# SH9_-_RS-485.net
KiCad netlist of a schematic drawn in Altium Designer
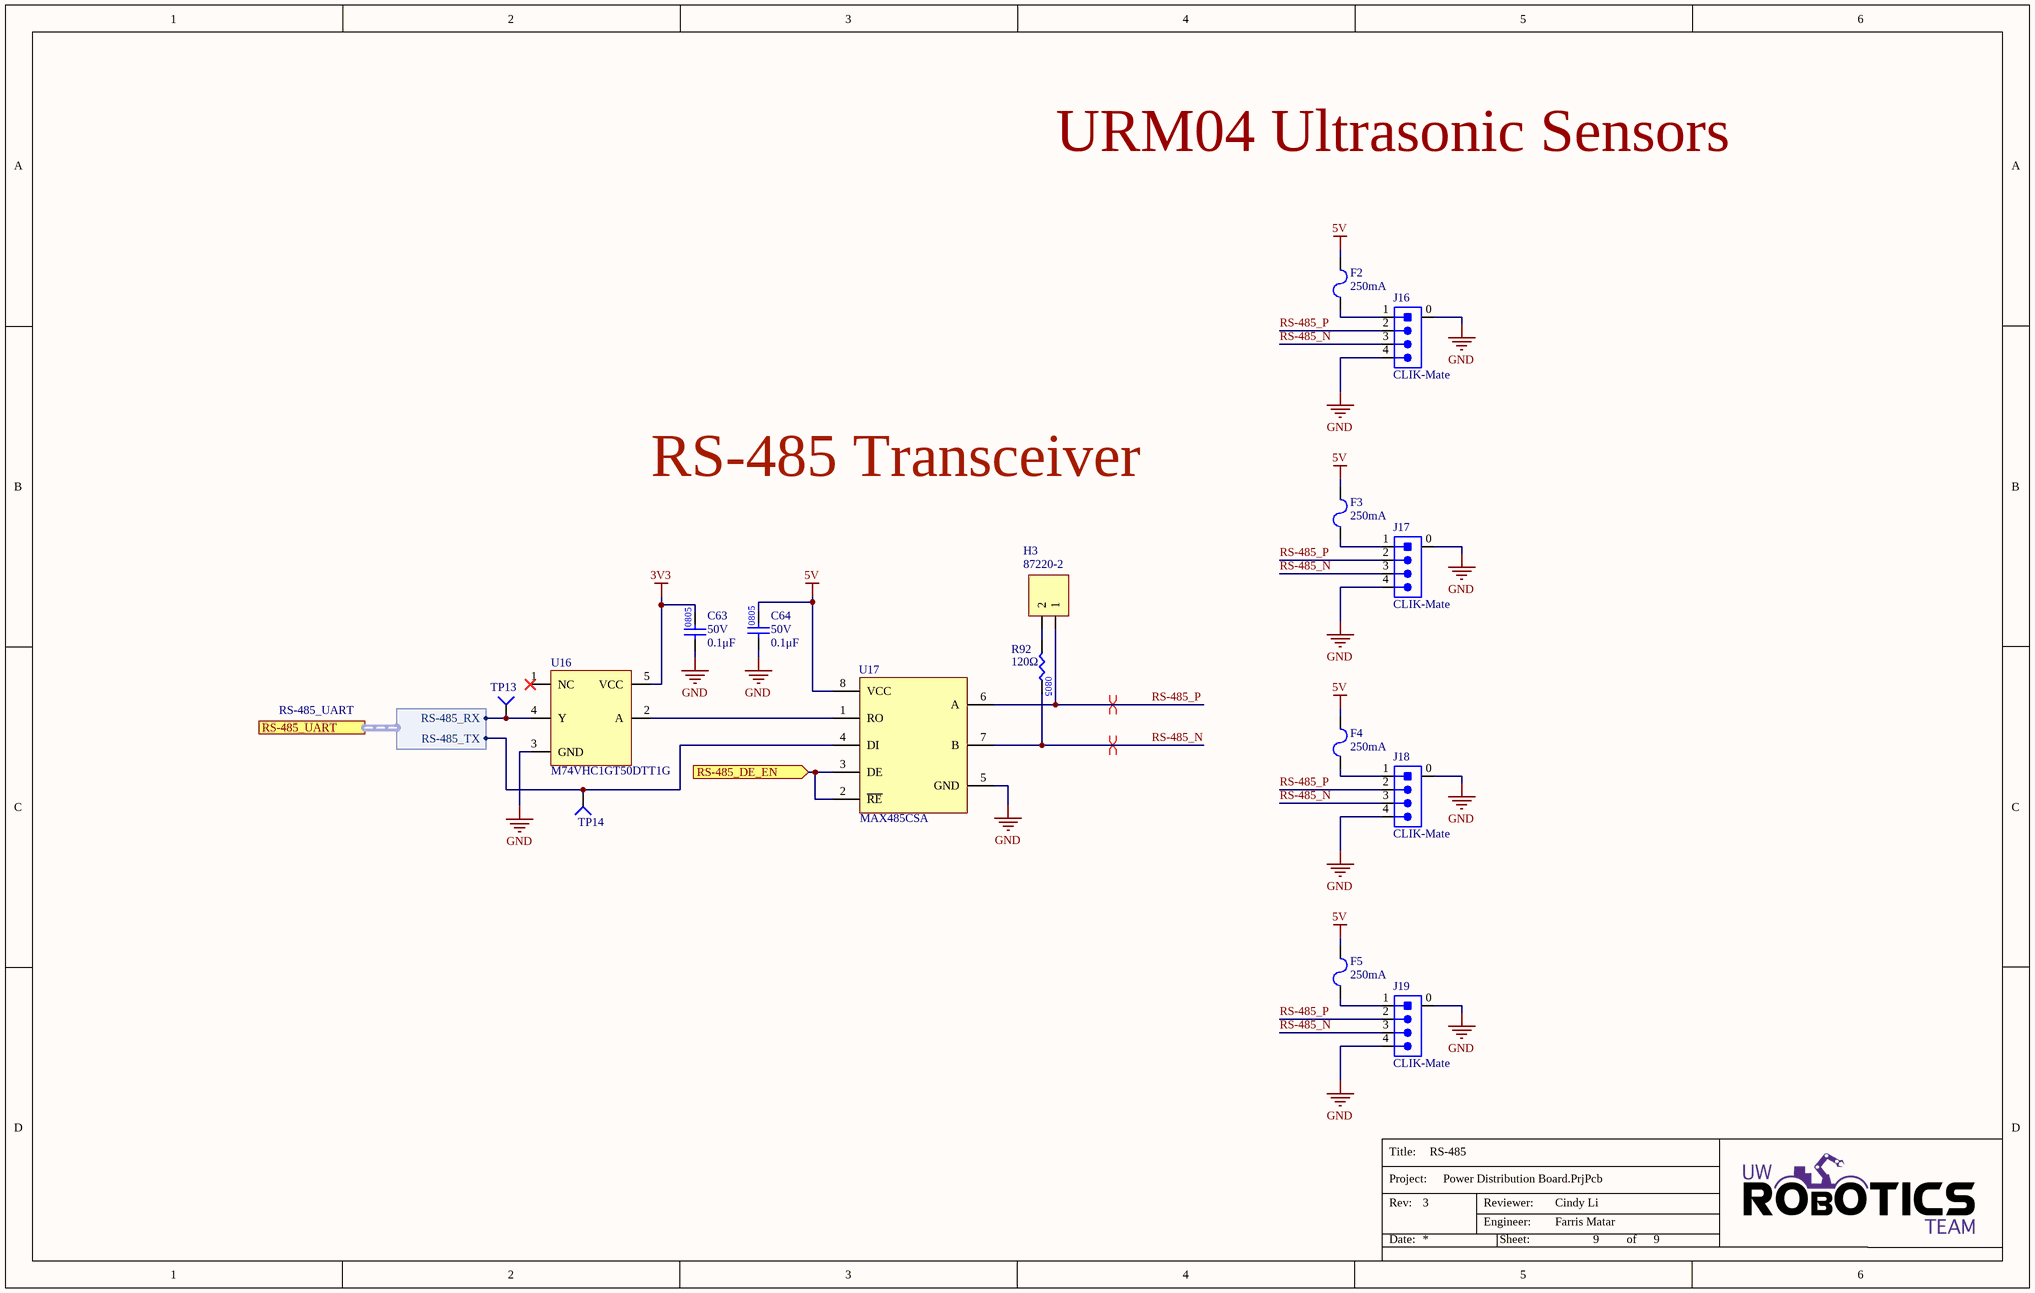
[diagram p0: SH9 - RS-485.SchDoc]

(export (version "E")
  (design (tool "Eeschema 10.0.6"))
  (components
    (comp (ref "C63")
      (value "0.1μF")
      (footprint "CAP2012")
      (description "CAP CER 0.1UF 50V X7R 0805")
      (fields
        (field (name "VOLTAGE RATING") "50V")
        (field (name "LCSC PART #") "C49678")
        (field (name "Comment") "CAP_0.1uF_50V_0805")
      )
      (libsource (lib "UWRT_Schematic_Library_2020") (part "CAP_0.1uF_50V_0805"))
    )
    (comp (ref "C64")
      (value "0.1μF")
      (footprint "CAP2012")
      (description "CAP CER 0.1UF 50V X7R 0805")
      (fields
        (field (name "VOLTAGE RATING") "50V")
        (field (name "LCSC PART #") "C49678")
        (field (name "Comment") "CAP_0.1uF_50V_0805")
      )
      (libsource (lib "UWRT_Schematic_Library_2020") (part "CAP_0.1uF_50V_0805"))
    )
    (comp (ref "F2")
      (value "FUSE_250mA_1206")
      (footprint "FUSE_1206")
      (description "FUSE BOARD MNT 250MA 125VAC/VDC")
      (fields (field (name "CURRENT RATING") "250mA"))
      (libsource (lib "UWRT_Schematic_Library_2020") (part "FUSE_250mA_1206"))
    )
    (comp (ref "F3")
      (value "FUSE_250mA_1206")
      (footprint "FUSE_1206")
      (description "FUSE BOARD MNT 250MA 125VAC/VDC")
      (fields (field (name "CURRENT RATING") "250mA"))
      (libsource (lib "UWRT_Schematic_Library_2020") (part "FUSE_250mA_1206"))
    )
    (comp (ref "F4")
      (value "FUSE_250mA_1206")
      (footprint "FUSE_1206")
      (description "FUSE BOARD MNT 250MA 125VAC/VDC")
      (fields (field (name "CURRENT RATING") "250mA"))
      (libsource (lib "UWRT_Schematic_Library_2020") (part "FUSE_250mA_1206"))
    )
    (comp (ref "F5")
      (value "FUSE_250mA_1206")
      (footprint "FUSE_1206")
      (description "FUSE BOARD MNT 250MA 125VAC/VDC")
      (fields (field (name "CURRENT RATING") "250mA"))
      (libsource (lib "UWRT_Schematic_Library_2020") (part "FUSE_250mA_1206"))
    )
    (comp (ref "H3")
      (value "JUMPER_2")
      (footprint "HDR1X2")
      (description "HEADER 2X1")
      (fields (field (name "MANUFACTURER PART NUMBER 1") "87220-2"))
      (libsource (lib "UWRT_Schematic_Library_2020") (part "JUMPER_2"))
    )
    (comp (ref "J16")
      (value "CON_4M_SM_RA")
      (footprint "MOLEX-5025850470")
      (description "CONN HEADER SMD RIGHT ANGLE 1.5 MM PITCH")
      (fields (field (name "FAMILY") "CLIK-Mate"))
      (libsource (lib "UWRT_Schematic_Library_2020") (part "CON_4M_SM_RA"))
    )
    (comp (ref "J17")
      (value "CON_4M_SM_RA")
      (footprint "MOLEX-5025850470")
      (description "CONN HEADER SMD RIGHT ANGLE 1.5 MM PITCH")
      (fields (field (name "FAMILY") "CLIK-Mate"))
      (libsource (lib "UWRT_Schematic_Library_2020") (part "CON_4M_SM_RA"))
    )
    (comp (ref "J18")
      (value "CON_4M_SM_RA")
      (footprint "MOLEX-5025850470")
      (description "CONN HEADER SMD RIGHT ANGLE 1.5 MM PITCH")
      (fields (field (name "FAMILY") "CLIK-Mate"))
      (libsource (lib "UWRT_Schematic_Library_2020") (part "CON_4M_SM_RA"))
    )
    (comp (ref "J19")
      (value "CON_4M_SM_RA")
      (footprint "MOLEX-5025850470")
      (description "CONN HEADER SMD RIGHT ANGLE 1.5 MM PITCH")
      (fields (field (name "FAMILY") "CLIK-Mate"))
      (libsource (lib "UWRT_Schematic_Library_2020") (part "CON_4M_SM_RA"))
    )
    (comp (ref "R92")
      (value "120Ω")
      (footprint "RES0805")
      (description "RES 120 OHM 1% 1/8W 0805")
      (fields (field (name "LCSC PART #") "C17437") (field (name "Comment") "RES_120Ω_0805_1%"))
      (libsource (lib "UWRT_Schematic_Library_2020") (part "RES_120Ω_0805_1%"))
    )
    (comp (ref "TP13")
      (value "TESTPOINT_1MM_CIRCLE")
      (footprint "TESTPOINT_CIRCLE_1MM")
      (description "TESTPOINT 1MM CIRCLE")
      (libsource (lib "UWRT_Schematic_Library_2020") (part "TESTPOINT_1MM_CIRCLE"))
    )
    (comp (ref "TP14")
      (value "TESTPOINT_1MM_CIRCLE")
      (footprint "TESTPOINT_CIRCLE_1MM")
      (description "TESTPOINT 1MM CIRCLE")
      (libsource (lib "UWRT_Schematic_Library_2020") (part "TESTPOINT_1MM_CIRCLE"))
    )
    (comp (ref "U16")
      (value "IC_BUFFER_TSOP5")
      (footprint "SN74LV1T34DBVR")
      (description "IC BUFFER NON-INVERT 5.5V 5TSOP")
      (fields (field (name "MANUFACTURER PART NUMBER 1") "M74VHC1GT50DTT1G"))
      (libsource (lib "UWRT_Schematic_Library_2020") (part "IC_BUFFER_TSOP5"))
    )
    (comp (ref "U17")
      (value "MAX485CSA")
      (footprint "SOIC127P600X175-8N")
      (description "IC RS485 TRANSCEIVER HALF 1/1 8SOIC")
      (fields (field (name "LCSC PART #") "C9945"))
      (libsource (lib "UWRT_Schematic_Library_2020") (part "MAX485CSA"))
    )
  )
  (nets
    (net (code "2") (name "/RS-485_DE_EN") (class "Default")
      (node (ref "U17") (pin "2") (pinfunction "~{RE}_2") (pintype "passive"))
      (node (ref "U17") (pin "3") (pinfunction "DE_3") (pintype "passive"))
    )
    (net (code "3") (name "/RS-485_N") (class "Default")
      (node (ref "J16") (pin "3") (pinfunction "3_3") (pintype "passive"))
      (node (ref "J17") (pin "3") (pinfunction "3_3") (pintype "passive"))
      (node (ref "J18") (pin "3") (pinfunction "3_3") (pintype "passive"))
      (node (ref "J19") (pin "3") (pinfunction "3_3") (pintype "passive"))
      (node (ref "R92") (pin "2") (pinfunction "2_2") (pintype "passive"))
      (node (ref "U17") (pin "7") (pinfunction "B_7") (pintype "passive"))
    )
    (net (code "4") (name "/RS-485_P") (class "Default")
      (node (ref "H3") (pin "1") (pinfunction "1_1") (pintype "passive"))
      (node (ref "J16") (pin "2") (pinfunction "2_2") (pintype "passive"))
      (node (ref "J17") (pin "2") (pinfunction "2_2") (pintype "passive"))
      (node (ref "J18") (pin "2") (pinfunction "2_2") (pintype "passive"))
      (node (ref "J19") (pin "2") (pinfunction "2_2") (pintype "passive"))
      (node (ref "U17") (pin "6") (pinfunction "A_6") (pintype "passive"))
    )
    (net (code "6") (name "3V3") (class "Default")
      (node (ref "C63") (pin "2") (pinfunction "2_2") (pintype "passive"))
      (node (ref "U16") (pin "5") (pinfunction "VCC_5") (pintype "passive"))
    )
    (net (code "7") (name "5V") (class "Default")
      (node (ref "C64") (pin "2") (pinfunction "2_2") (pintype "passive"))
      (node (ref "F2") (pin "2") (pinfunction "2_2") (pintype "passive"))
      (node (ref "F3") (pin "2") (pinfunction "2_2") (pintype "passive"))
      (node (ref "F4") (pin "2") (pinfunction "2_2") (pintype "passive"))
      (node (ref "F5") (pin "2") (pinfunction "2_2") (pintype "passive"))
      (node (ref "U17") (pin "8") (pinfunction "VCC_8") (pintype "power_in"))
    )
    (net (code "8") (name "GND") (class "Default")
      (node (ref "C63") (pin "1") (pinfunction "1_1") (pintype "passive"))
      (node (ref "C64") (pin "1") (pinfunction "1_1") (pintype "passive"))
      (node (ref "J16") (pin "0") (pinfunction "0_0") (pintype "passive"))
      (node (ref "J16") (pin "4") (pinfunction "4_4") (pintype "passive"))
      (node (ref "J17") (pin "0") (pinfunction "0_0") (pintype "passive"))
      (node (ref "J17") (pin "4") (pinfunction "4_4") (pintype "passive"))
      (node (ref "J18") (pin "0") (pinfunction "0_0") (pintype "passive"))
      (node (ref "J18") (pin "4") (pinfunction "4_4") (pintype "passive"))
      (node (ref "J19") (pin "0") (pinfunction "0_0") (pintype "passive"))
      (node (ref "J19") (pin "4") (pinfunction "4_4") (pintype "passive"))
      (node (ref "U16") (pin "3") (pinfunction "GND_3") (pintype "passive"))
      (node (ref "U17") (pin "5") (pinfunction "GND_5") (pintype "power_in"))
    )
    (net (code "9") (name "Net-(F2-Pad1)") (class "Default")
      (node (ref "F2") (pin "1") (pinfunction "1_1") (pintype "passive"))
      (node (ref "J16") (pin "1") (pinfunction "1_1") (pintype "passive"))
    )
    (net (code "10") (name "Net-(F3-Pad1)") (class "Default")
      (node (ref "F3") (pin "1") (pinfunction "1_1") (pintype "passive"))
      (node (ref "J17") (pin "1") (pinfunction "1_1") (pintype "passive"))
    )
    (net (code "11") (name "Net-(F4-Pad1)") (class "Default")
      (node (ref "F4") (pin "1") (pinfunction "1_1") (pintype "passive"))
      (node (ref "J18") (pin "1") (pinfunction "1_1") (pintype "passive"))
    )
    (net (code "12") (name "Net-(F5-Pad1)") (class "Default")
      (node (ref "F5") (pin "1") (pinfunction "1_1") (pintype "passive"))
      (node (ref "J19") (pin "1") (pinfunction "1_1") (pintype "passive"))
    )
    (net (code "13") (name "Net-(H3-Pad2)") (class "Default")
      (node (ref "H3") (pin "2") (pinfunction "2_2") (pintype "passive"))
      (node (ref "R92") (pin "1") (pinfunction "1_1") (pintype "passive"))
    )
    (net (code "14") (name "Net-(TP13-=value)") (class "Default")
      (node (ref "TP13") (pin "1") (pinfunction "=value_1") (pintype "passive"))
      (node (ref "U16") (pin "4") (pinfunction "Y_4") (pintype "passive"))
    )
    (net (code "15") (name "Net-(TP14-=value)") (class "Default")
      (node (ref "TP14") (pin "1") (pinfunction "=value_1") (pintype "passive"))
      (node (ref "U17") (pin "4") (pinfunction "DI_4") (pintype "passive"))
    )
    (net (code "16") (name "Net-(U16-A)") (class "Default")
      (node (ref "U16") (pin "2") (pinfunction "A_2") (pintype "passive"))
      (node (ref "U17") (pin "1") (pinfunction "RO_1") (pintype "passive"))
    )
    (net (code "17") (name "unconnected-(U16-NC-Pad1)") (class "Default")
      (node (ref "U16") (pin "1") (pinfunction "NC_1") (pintype "passive+no_connect"))
    )
  )
)
